# lipovsky-power.net
KiCad netlist of a schematic drawn in EAGLE
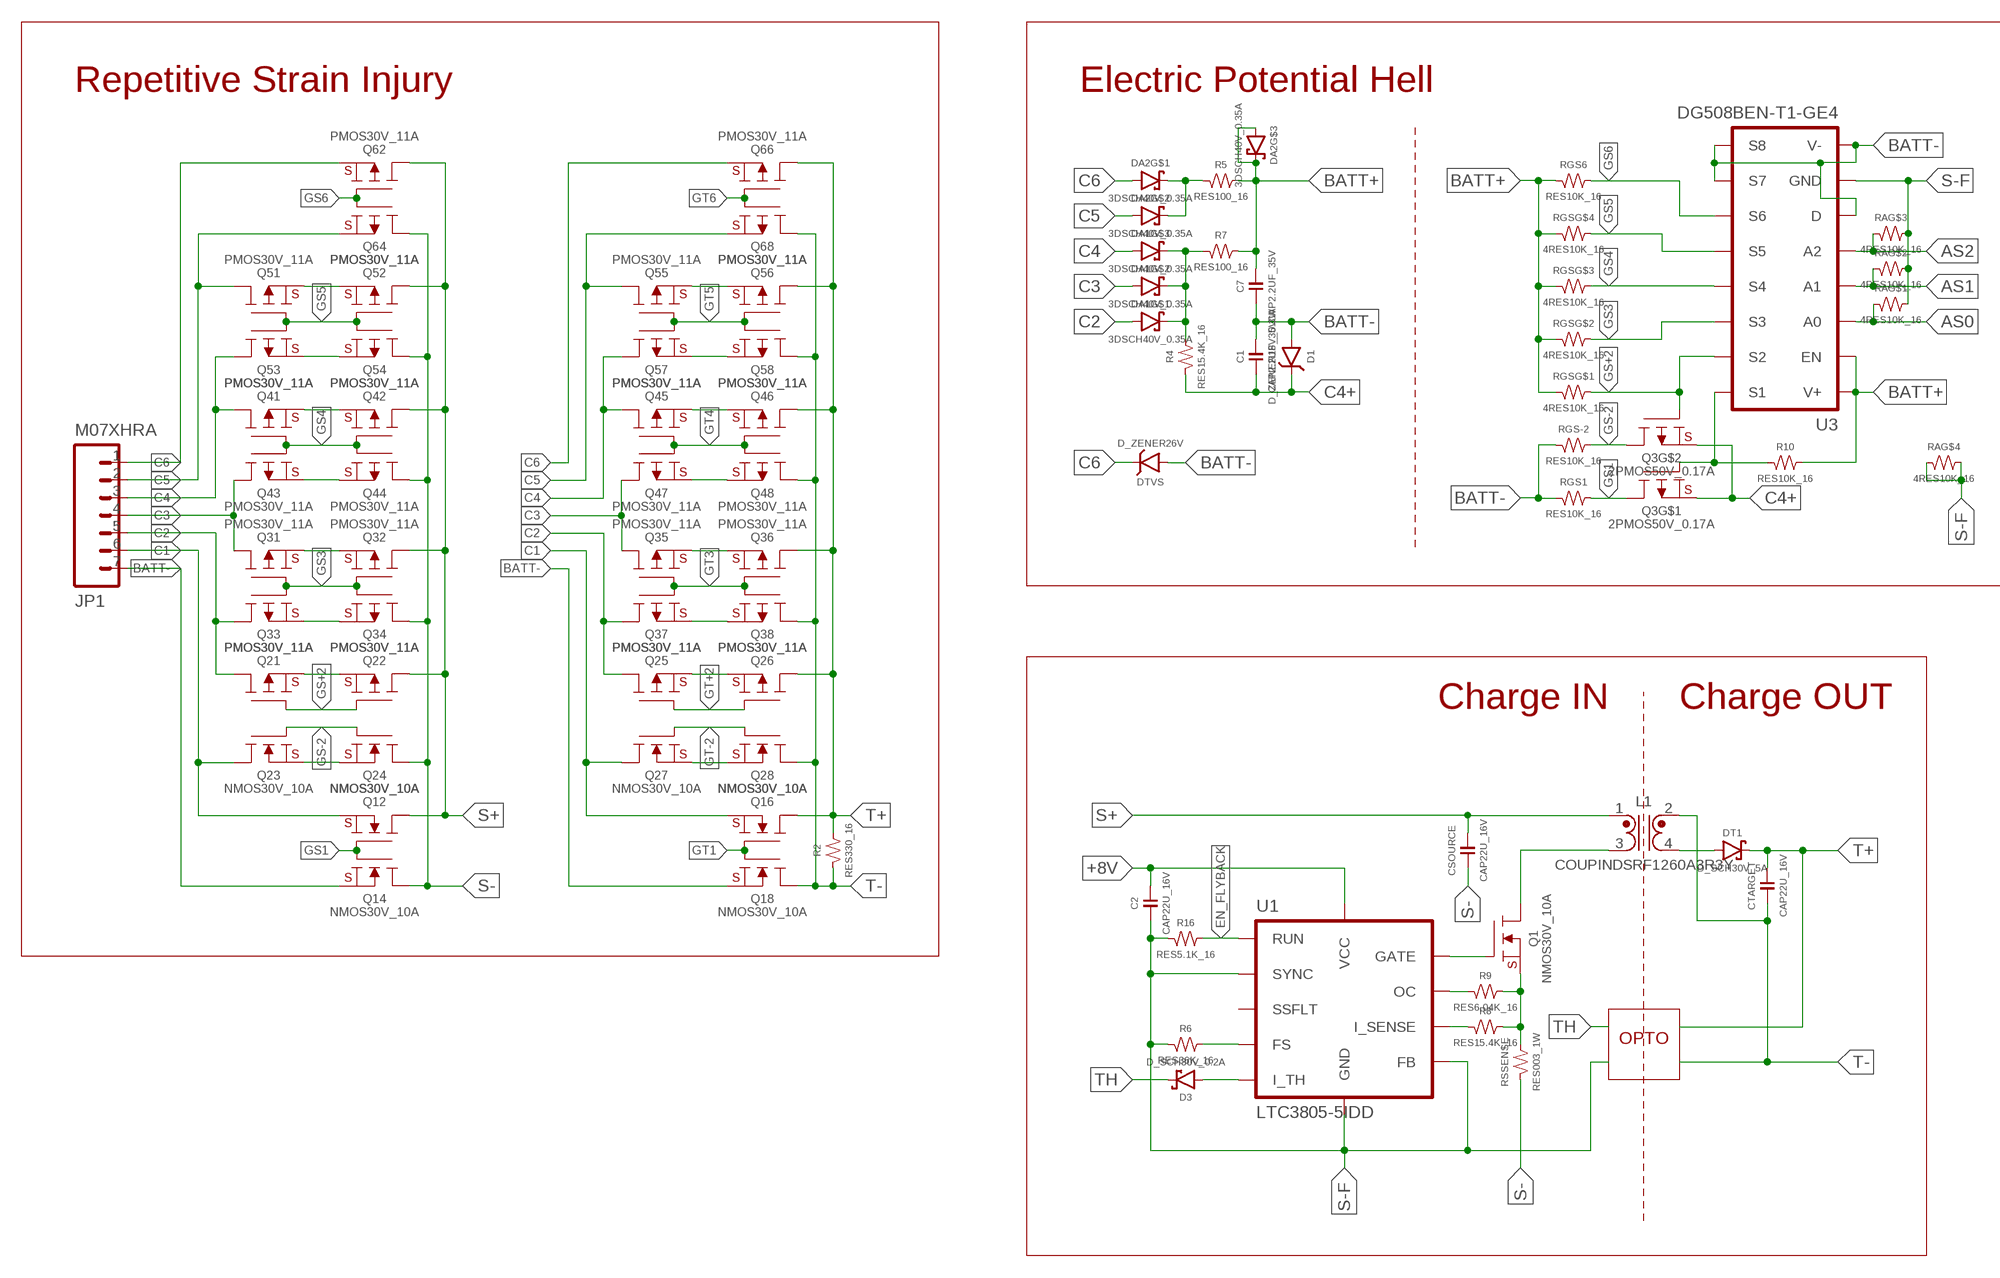
[diagram p0: schematic, sheet 1, part 1 of 2]
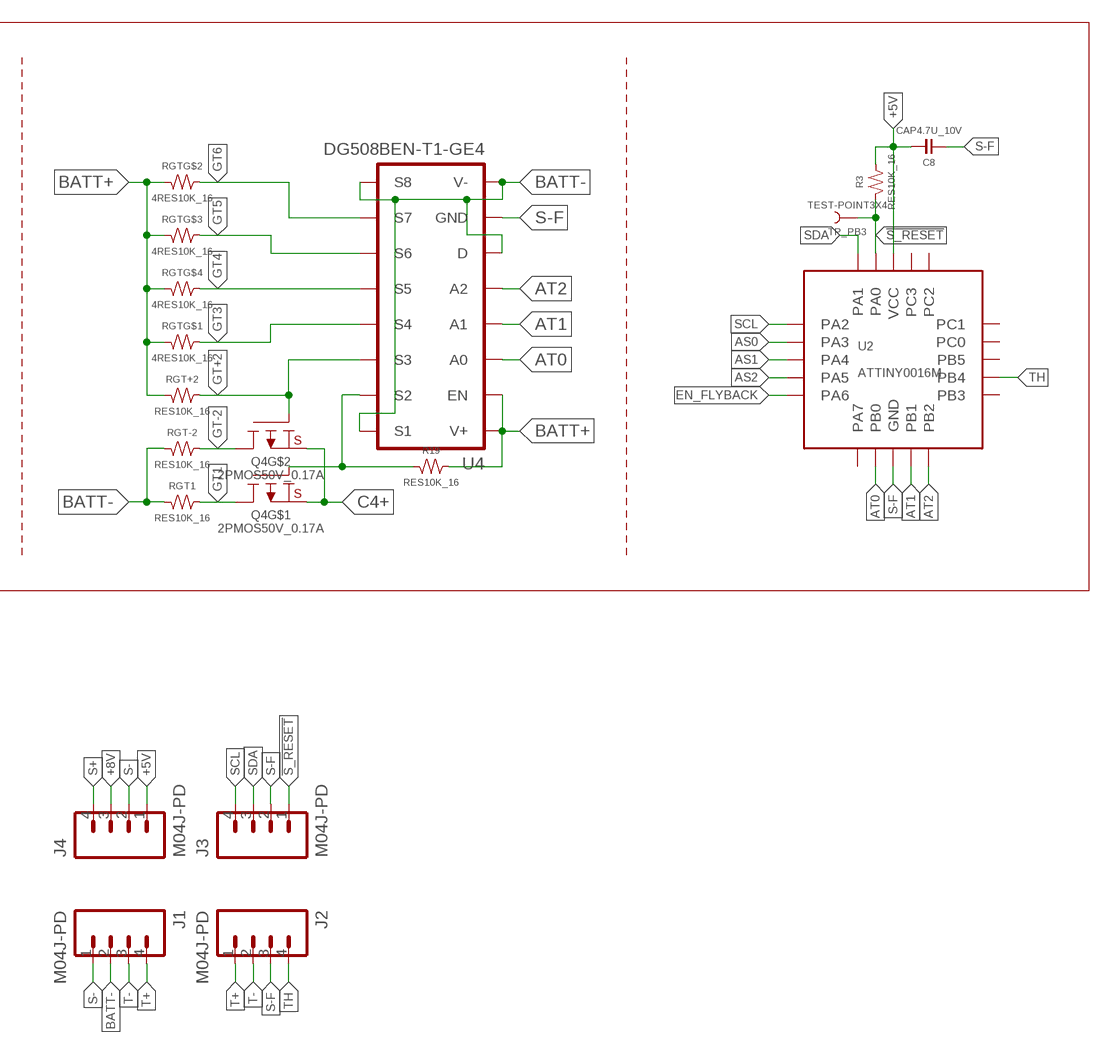
[diagram p1: schematic, sheet 1, part 2 of 2]

(export (version "E")
  (design (tool "Eeschema 10.0.6"))
  (components
    (comp (ref "C1")
      (value "CAP2.2UF_35V")
      (footprint "eagle-import:0402")
      (fields
        (field (name "DIGIKEY_PART_#") "445-9028-1-ND")
        (field (name "MANUFACTURER") "TDK Corporation")
        (field (name "MFG_PART_#") "C1005X5R1V225K050BC")
      )
      (libsource (lib "eagle-import") (part "CAP2.2UF_35V"))
    )
    (comp (ref "C2")
      (value "CAP22U_16V")
      (footprint "eagle-import:0805")
      (fields
        (field (name "DIGIKEY_PART_#") "1276-6780-1-ND")
        (field (name "MANUFACTURER") "Samsung Electro-Mechanics America, Inc.")
        (field (name "MFG_PART_#") "CL21A226MOCLRNC")
      )
      (libsource (lib "eagle-import") (part "CAP22U_16V"))
    )
    (comp (ref "C7")
      (value "CAP2.2UF_35V")
      (footprint "eagle-import:0402")
      (fields
        (field (name "DIGIKEY_PART_#") "445-9028-1-ND")
        (field (name "MANUFACTURER") "TDK Corporation")
        (field (name "MFG_PART_#") "C1005X5R1V225K050BC")
      )
      (libsource (lib "eagle-import") (part "CAP2.2UF_35V"))
    )
    (comp (ref "C8")
      (value "CAP4.7U_10V")
      (footprint "eagle-import:0603")
      (fields
        (field (name "DIGIKEY_PART_#") "587-1441-1-ND")
        (field (name "MANUFACTURER") "Taiyo Yuden")
        (field (name "MFG_PART_#") "LMK107BJ475KA-T")
      )
      (libsource (lib "eagle-import") (part "CAP4.7U_10V"))
    )
    (comp (ref "CSOURCE")
      (value "CAP22U_16V")
      (footprint "eagle-import:0805")
      (fields
        (field (name "DIGIKEY_PART_#") "1276-6780-1-ND")
        (field (name "MANUFACTURER") "Samsung Electro-Mechanics America, Inc.")
        (field (name "MFG_PART_#") "CL21A226MOCLRNC")
      )
      (libsource (lib "eagle-import") (part "CAP22U_16V"))
    )
    (comp (ref "CTARGET")
      (value "CAP22U_16V")
      (footprint "eagle-import:0805")
      (fields
        (field (name "DIGIKEY_PART_#") "1276-6780-1-ND")
        (field (name "MANUFACTURER") "Samsung Electro-Mechanics America, Inc.")
        (field (name "MFG_PART_#") "CL21A226MOCLRNC")
      )
      (libsource (lib "eagle-import") (part "CAP22U_16V"))
    )
    (comp (ref "D1")
      (value "D_ZENER18V_0.3W")
      (footprint "eagle-import:SOD323+")
      (fields
        (field (name "DIGIKEY_PART_#") "MM3Z18VT1GOSCT-ND")
        (field (name "MANUFACTURER") "ON Semiconductor")
        (field (name "MFG_PART_#") "MM3Z18VT1G")
      )
      (libsource (lib "eagle-import") (part "D_ZENER18V_0.3W"))
    )
    (comp (ref "D3")
      (value "D_SCH30V_0.2A")
      (footprint "eagle-import:SOD523+")
      (fields
        (field (name "DIGIKEY_PART_#") "RB531SM-30T2RCT-ND")
        (field (name "MANUFACTURER") "Rohm Semiconductor")
        (field (name "MFG_PART_#") "RB531SM-30T2R")
      )
      (libsource (lib "eagle-import") (part "D_SCH30V_0.2A"))
    )
    (comp (ref "DA1")
      (value "3DSCH40V_0.35A")
      (footprint "eagle-import:SOT-363")
      (fields
        (field (name "DIGIKEY_PART_#") "SD103ATW-FDICT-ND")
        (field (name "MANUFACTURER") "Diodes Incorporated")
        (field (name "MFG_PART_#") "SD103ATW-7-F")
      )
      (libsource (lib "eagle-import") (part "3DSCH40V_0.35A"))
    )
    (comp (ref "DA2")
      (value "3DSCH40V_0.35A")
      (footprint "eagle-import:SOT-363")
      (fields
        (field (name "DIGIKEY_PART_#") "SD103ATW-FDICT-ND")
        (field (name "MANUFACTURER") "Diodes Incorporated")
        (field (name "MFG_PART_#") "SD103ATW-7-F")
      )
      (libsource (lib "eagle-import") (part "3DSCH40V_0.35A"))
    )
    (comp (ref "DT1")
      (value "D_SCH30V_5A")
      (footprint "eagle-import:SOD-128")
      (fields
        (field (name "DIGIKEY_PART_#") "1727-5317-1-ND")
        (field (name "MANUFACTURER") "Nexperia USA Inc.")
        (field (name "MFG_PART_#") "PMEG3050EP,115")
      )
      (libsource (lib "eagle-import") (part "D_SCH30V_5A"))
    )
    (comp (ref "DTVS")
      (value "D_ZENER26V")
      (footprint "eagle-import:2-UDFN")
      (fields
        (field (name "DIGIKEY_PART_#") "D26V0H1U2LP20-7DICT-ND")
        (field (name "MANUFACTURER") "Diodes Incorporated")
        (field (name "MFG_PART_#") "D26V0H1U2LP20-7")
      )
      (libsource (lib "eagle-import") (part "D_ZENER26V"))
    )
    (comp (ref "J1")
      (value "M04J-PD")
      (footprint "eagle-import:1X04_929J")
      (fields
        (field (name "DIGIKEY_PART_#") "801-87-004-10-012101-ND")
        (field (name "MANUFACTURER") "Preci-Dip")
        (field (name "MFG_PART_#") "801-87-004-10-012101")
      )
      (libsource (lib "eagle-import") (part "M04J-PD"))
    )
    (comp (ref "J2")
      (value "M04J-PD")
      (footprint "eagle-import:1X04_929J")
      (fields
        (field (name "DIGIKEY_PART_#") "801-87-004-10-012101-ND")
        (field (name "MANUFACTURER") "Preci-Dip")
        (field (name "MFG_PART_#") "801-87-004-10-012101")
      )
      (libsource (lib "eagle-import") (part "M04J-PD"))
    )
    (comp (ref "J3")
      (value "M04J-PD")
      (footprint "eagle-import:1X04_929J")
      (fields
        (field (name "DIGIKEY_PART_#") "801-87-004-10-012101-ND")
        (field (name "MANUFACTURER") "Preci-Dip")
        (field (name "MFG_PART_#") "801-87-004-10-012101")
      )
      (libsource (lib "eagle-import") (part "M04J-PD"))
    )
    (comp (ref "J4")
      (value "M04J-PD")
      (footprint "eagle-import:1X04_929J")
      (fields
        (field (name "DIGIKEY_PART_#") "801-87-004-10-012101-ND")
        (field (name "MANUFACTURER") "Preci-Dip")
        (field (name "MFG_PART_#") "801-87-004-10-012101")
      )
      (libsource (lib "eagle-import") (part "M04J-PD"))
    )
    (comp (ref "JP1")
      (value "M07XHRA")
      (footprint "eagle-import:XH07-RA")
      (fields
        (field (name "DIGIKEY_PART_#") "455-2240-ND")
        (field (name "MANUFACTURER") "JST Sales America Inc.")
        (field (name "MFG_PART_#") "S7B-XH-A(LF)(SN)")
      )
      (libsource (lib "eagle-import") (part "M07XHRA"))
    )
    (comp (ref "L1")
      (value "COUPINDSRF1260A3R3Y")
      (footprint "eagle-import:SRF1260A")
      (fields
        (field (name "DIGIKEY_PART_#") "SRF1260A-3R3YCT-ND")
        (field (name "MANUFACTURER") "Bourns Inc.")
        (field (name "MFG_PART_#") "SRF1260A-3R3Y")
      )
      (libsource (lib "eagle-import") (part "COUPINDSRF1260A3R3Y"))
    )
    (comp (ref "Q1")
      (value "NMOS30V_10A")
      (footprint "eagle-import:6-POWERWDFN")
      (fields
        (field (name "DIGIKEY_PART_#") "FDMA7670CT-ND")
        (field (name "MANUFACTURER") "Fairchild Semiconductor")
        (field (name "MFG_PART_#") "FDMA7670")
      )
      (libsource (lib "eagle-import") (part "NMOS30V_10A"))
    )
    (comp (ref "Q3")
      (value "2PMOS50V_0.17A")
      (footprint "eagle-import:SOT-666")
      (fields
        (field (name "DIGIKEY_PART_#") "568-10474-1-ND")
        (field (name "MANUFACTURER") "NXP Semiconductors")
        (field (name "MFG_PART_#") "BSS84AKV,115")
      )
      (libsource (lib "eagle-import") (part "2PMOS50V_0.17A"))
    )
    (comp (ref "Q4")
      (value "2PMOS50V_0.17A")
      (footprint "eagle-import:SOT-666")
      (fields
        (field (name "DIGIKEY_PART_#") "568-10474-1-ND")
        (field (name "MANUFACTURER") "NXP Semiconductors")
        (field (name "MFG_PART_#") "BSS84AKV,115")
      )
      (libsource (lib "eagle-import") (part "2PMOS50V_0.17A"))
    )
    (comp (ref "Q12")
      (value "NMOS30V_10A")
      (footprint "eagle-import:6-POWERWDFN")
      (fields
        (field (name "DIGIKEY_PART_#") "FDMA7670CT-ND")
        (field (name "MANUFACTURER") "Fairchild Semiconductor")
        (field (name "MFG_PART_#") "FDMA7670")
      )
      (libsource (lib "eagle-import") (part "NMOS30V_10A"))
    )
    (comp (ref "Q14")
      (value "NMOS30V_10A")
      (footprint "eagle-import:6-POWERWDFN")
      (fields
        (field (name "DIGIKEY_PART_#") "FDMA7670CT-ND")
        (field (name "MANUFACTURER") "Fairchild Semiconductor")
        (field (name "MFG_PART_#") "FDMA7670")
      )
      (libsource (lib "eagle-import") (part "NMOS30V_10A"))
    )
    (comp (ref "Q16")
      (value "NMOS30V_10A")
      (footprint "eagle-import:6-POWERWDFN")
      (fields
        (field (name "DIGIKEY_PART_#") "FDMA7670CT-ND")
        (field (name "MANUFACTURER") "Fairchild Semiconductor")
        (field (name "MFG_PART_#") "FDMA7670")
      )
      (libsource (lib "eagle-import") (part "NMOS30V_10A"))
    )
    (comp (ref "Q18")
      (value "NMOS30V_10A")
      (footprint "eagle-import:6-POWERWDFN")
      (fields
        (field (name "DIGIKEY_PART_#") "FDMA7670CT-ND")
        (field (name "MANUFACTURER") "Fairchild Semiconductor")
        (field (name "MFG_PART_#") "FDMA7670")
      )
      (libsource (lib "eagle-import") (part "NMOS30V_10A"))
    )
    (comp (ref "Q21")
      (value "PMOS30V_11A")
      (footprint "eagle-import:6-POWERWDFN")
      (fields
        (field (name "DIGIKEY_PART_#") "FDMA6676PZCT-ND")
        (field (name "MANUFACTURER") "Fairchild Semiconductor")
        (field (name "MFG_PART_#") "FDMA6676PZ")
      )
      (libsource (lib "eagle-import") (part "PMOS30V_11A"))
    )
    (comp (ref "Q22")
      (value "PMOS30V_11A")
      (footprint "eagle-import:6-POWERWDFN")
      (fields
        (field (name "DIGIKEY_PART_#") "FDMA6676PZCT-ND")
        (field (name "MANUFACTURER") "Fairchild Semiconductor")
        (field (name "MFG_PART_#") "FDMA6676PZ")
      )
      (libsource (lib "eagle-import") (part "PMOS30V_11A"))
    )
    (comp (ref "Q23")
      (value "NMOS30V_10A")
      (footprint "eagle-import:6-POWERWDFN")
      (fields
        (field (name "DIGIKEY_PART_#") "FDMA7670CT-ND")
        (field (name "MANUFACTURER") "Fairchild Semiconductor")
        (field (name "MFG_PART_#") "FDMA7670")
      )
      (libsource (lib "eagle-import") (part "NMOS30V_10A"))
    )
    (comp (ref "Q24")
      (value "NMOS30V_10A")
      (footprint "eagle-import:6-POWERWDFN")
      (fields
        (field (name "DIGIKEY_PART_#") "FDMA7670CT-ND")
        (field (name "MANUFACTURER") "Fairchild Semiconductor")
        (field (name "MFG_PART_#") "FDMA7670")
      )
      (libsource (lib "eagle-import") (part "NMOS30V_10A"))
    )
    (comp (ref "Q25")
      (value "PMOS30V_11A")
      (footprint "eagle-import:6-POWERWDFN")
      (fields
        (field (name "DIGIKEY_PART_#") "FDMA6676PZCT-ND")
        (field (name "MANUFACTURER") "Fairchild Semiconductor")
        (field (name "MFG_PART_#") "FDMA6676PZ")
      )
      (libsource (lib "eagle-import") (part "PMOS30V_11A"))
    )
    (comp (ref "Q26")
      (value "PMOS30V_11A")
      (footprint "eagle-import:6-POWERWDFN")
      (fields
        (field (name "DIGIKEY_PART_#") "FDMA6676PZCT-ND")
        (field (name "MANUFACTURER") "Fairchild Semiconductor")
        (field (name "MFG_PART_#") "FDMA6676PZ")
      )
      (libsource (lib "eagle-import") (part "PMOS30V_11A"))
    )
    (comp (ref "Q27")
      (value "NMOS30V_10A")
      (footprint "eagle-import:6-POWERWDFN")
      (fields
        (field (name "DIGIKEY_PART_#") "FDMA7670CT-ND")
        (field (name "MANUFACTURER") "Fairchild Semiconductor")
        (field (name "MFG_PART_#") "FDMA7670")
      )
      (libsource (lib "eagle-import") (part "NMOS30V_10A"))
    )
    (comp (ref "Q28")
      (value "NMOS30V_10A")
      (footprint "eagle-import:6-POWERWDFN")
      (fields
        (field (name "DIGIKEY_PART_#") "FDMA7670CT-ND")
        (field (name "MANUFACTURER") "Fairchild Semiconductor")
        (field (name "MFG_PART_#") "FDMA7670")
      )
      (libsource (lib "eagle-import") (part "NMOS30V_10A"))
    )
    (comp (ref "Q31")
      (value "PMOS30V_11A")
      (footprint "eagle-import:6-POWERWDFN")
      (fields
        (field (name "DIGIKEY_PART_#") "FDMA6676PZCT-ND")
        (field (name "MANUFACTURER") "Fairchild Semiconductor")
        (field (name "MFG_PART_#") "FDMA6676PZ")
      )
      (libsource (lib "eagle-import") (part "PMOS30V_11A"))
    )
    (comp (ref "Q32")
      (value "PMOS30V_11A")
      (footprint "eagle-import:6-POWERWDFN")
      (fields
        (field (name "DIGIKEY_PART_#") "FDMA6676PZCT-ND")
        (field (name "MANUFACTURER") "Fairchild Semiconductor")
        (field (name "MFG_PART_#") "FDMA6676PZ")
      )
      (libsource (lib "eagle-import") (part "PMOS30V_11A"))
    )
    (comp (ref "Q33")
      (value "PMOS30V_11A")
      (footprint "eagle-import:6-POWERWDFN")
      (fields
        (field (name "DIGIKEY_PART_#") "FDMA6676PZCT-ND")
        (field (name "MANUFACTURER") "Fairchild Semiconductor")
        (field (name "MFG_PART_#") "FDMA6676PZ")
      )
      (libsource (lib "eagle-import") (part "PMOS30V_11A"))
    )
    (comp (ref "Q34")
      (value "PMOS30V_11A")
      (footprint "eagle-import:6-POWERWDFN")
      (fields
        (field (name "DIGIKEY_PART_#") "FDMA6676PZCT-ND")
        (field (name "MANUFACTURER") "Fairchild Semiconductor")
        (field (name "MFG_PART_#") "FDMA6676PZ")
      )
      (libsource (lib "eagle-import") (part "PMOS30V_11A"))
    )
    (comp (ref "Q35")
      (value "PMOS30V_11A")
      (footprint "eagle-import:6-POWERWDFN")
      (fields
        (field (name "DIGIKEY_PART_#") "FDMA6676PZCT-ND")
        (field (name "MANUFACTURER") "Fairchild Semiconductor")
        (field (name "MFG_PART_#") "FDMA6676PZ")
      )
      (libsource (lib "eagle-import") (part "PMOS30V_11A"))
    )
    (comp (ref "Q36")
      (value "PMOS30V_11A")
      (footprint "eagle-import:6-POWERWDFN")
      (fields
        (field (name "DIGIKEY_PART_#") "FDMA6676PZCT-ND")
        (field (name "MANUFACTURER") "Fairchild Semiconductor")
        (field (name "MFG_PART_#") "FDMA6676PZ")
      )
      (libsource (lib "eagle-import") (part "PMOS30V_11A"))
    )
    (comp (ref "Q37")
      (value "PMOS30V_11A")
      (footprint "eagle-import:6-POWERWDFN")
      (fields
        (field (name "DIGIKEY_PART_#") "FDMA6676PZCT-ND")
        (field (name "MANUFACTURER") "Fairchild Semiconductor")
        (field (name "MFG_PART_#") "FDMA6676PZ")
      )
      (libsource (lib "eagle-import") (part "PMOS30V_11A"))
    )
    (comp (ref "Q38")
      (value "PMOS30V_11A")
      (footprint "eagle-import:6-POWERWDFN")
      (fields
        (field (name "DIGIKEY_PART_#") "FDMA6676PZCT-ND")
        (field (name "MANUFACTURER") "Fairchild Semiconductor")
        (field (name "MFG_PART_#") "FDMA6676PZ")
      )
      (libsource (lib "eagle-import") (part "PMOS30V_11A"))
    )
    (comp (ref "Q41")
      (value "PMOS30V_11A")
      (footprint "eagle-import:6-POWERWDFN")
      (fields
        (field (name "DIGIKEY_PART_#") "FDMA6676PZCT-ND")
        (field (name "MANUFACTURER") "Fairchild Semiconductor")
        (field (name "MFG_PART_#") "FDMA6676PZ")
      )
      (libsource (lib "eagle-import") (part "PMOS30V_11A"))
    )
    (comp (ref "Q42")
      (value "PMOS30V_11A")
      (footprint "eagle-import:6-POWERWDFN")
      (fields
        (field (name "DIGIKEY_PART_#") "FDMA6676PZCT-ND")
        (field (name "MANUFACTURER") "Fairchild Semiconductor")
        (field (name "MFG_PART_#") "FDMA6676PZ")
      )
      (libsource (lib "eagle-import") (part "PMOS30V_11A"))
    )
    (comp (ref "Q43")
      (value "PMOS30V_11A")
      (footprint "eagle-import:6-POWERWDFN")
      (fields
        (field (name "DIGIKEY_PART_#") "FDMA6676PZCT-ND")
        (field (name "MANUFACTURER") "Fairchild Semiconductor")
        (field (name "MFG_PART_#") "FDMA6676PZ")
      )
      (libsource (lib "eagle-import") (part "PMOS30V_11A"))
    )
    (comp (ref "Q44")
      (value "PMOS30V_11A")
      (footprint "eagle-import:6-POWERWDFN")
      (fields
        (field (name "DIGIKEY_PART_#") "FDMA6676PZCT-ND")
        (field (name "MANUFACTURER") "Fairchild Semiconductor")
        (field (name "MFG_PART_#") "FDMA6676PZ")
      )
      (libsource (lib "eagle-import") (part "PMOS30V_11A"))
    )
    (comp (ref "Q45")
      (value "PMOS30V_11A")
      (footprint "eagle-import:6-POWERWDFN")
      (fields
        (field (name "DIGIKEY_PART_#") "FDMA6676PZCT-ND")
        (field (name "MANUFACTURER") "Fairchild Semiconductor")
        (field (name "MFG_PART_#") "FDMA6676PZ")
      )
      (libsource (lib "eagle-import") (part "PMOS30V_11A"))
    )
    (comp (ref "Q46")
      (value "PMOS30V_11A")
      (footprint "eagle-import:6-POWERWDFN")
      (fields
        (field (name "DIGIKEY_PART_#") "FDMA6676PZCT-ND")
        (field (name "MANUFACTURER") "Fairchild Semiconductor")
        (field (name "MFG_PART_#") "FDMA6676PZ")
      )
      (libsource (lib "eagle-import") (part "PMOS30V_11A"))
    )
    (comp (ref "Q47")
      (value "PMOS30V_11A")
      (footprint "eagle-import:6-POWERWDFN")
      (fields
        (field (name "DIGIKEY_PART_#") "FDMA6676PZCT-ND")
        (field (name "MANUFACTURER") "Fairchild Semiconductor")
        (field (name "MFG_PART_#") "FDMA6676PZ")
      )
      (libsource (lib "eagle-import") (part "PMOS30V_11A"))
    )
    (comp (ref "Q48")
      (value "PMOS30V_11A")
      (footprint "eagle-import:6-POWERWDFN")
      (fields
        (field (name "DIGIKEY_PART_#") "FDMA6676PZCT-ND")
        (field (name "MANUFACTURER") "Fairchild Semiconductor")
        (field (name "MFG_PART_#") "FDMA6676PZ")
      )
      (libsource (lib "eagle-import") (part "PMOS30V_11A"))
    )
    (comp (ref "Q51")
      (value "PMOS30V_11A")
      (footprint "eagle-import:6-POWERWDFN")
      (fields
        (field (name "DIGIKEY_PART_#") "FDMA6676PZCT-ND")
        (field (name "MANUFACTURER") "Fairchild Semiconductor")
        (field (name "MFG_PART_#") "FDMA6676PZ")
      )
      (libsource (lib "eagle-import") (part "PMOS30V_11A"))
    )
    (comp (ref "Q52")
      (value "PMOS30V_11A")
      (footprint "eagle-import:6-POWERWDFN")
      (fields
        (field (name "DIGIKEY_PART_#") "FDMA6676PZCT-ND")
        (field (name "MANUFACTURER") "Fairchild Semiconductor")
        (field (name "MFG_PART_#") "FDMA6676PZ")
      )
      (libsource (lib "eagle-import") (part "PMOS30V_11A"))
    )
    (comp (ref "Q53")
      (value "PMOS30V_11A")
      (footprint "eagle-import:6-POWERWDFN")
      (fields
        (field (name "DIGIKEY_PART_#") "FDMA6676PZCT-ND")
        (field (name "MANUFACTURER") "Fairchild Semiconductor")
        (field (name "MFG_PART_#") "FDMA6676PZ")
      )
      (libsource (lib "eagle-import") (part "PMOS30V_11A"))
    )
    (comp (ref "Q54")
      (value "PMOS30V_11A")
      (footprint "eagle-import:6-POWERWDFN")
      (fields
        (field (name "DIGIKEY_PART_#") "FDMA6676PZCT-ND")
        (field (name "MANUFACTURER") "Fairchild Semiconductor")
        (field (name "MFG_PART_#") "FDMA6676PZ")
      )
      (libsource (lib "eagle-import") (part "PMOS30V_11A"))
    )
    (comp (ref "Q55")
      (value "PMOS30V_11A")
      (footprint "eagle-import:6-POWERWDFN")
      (fields
        (field (name "DIGIKEY_PART_#") "FDMA6676PZCT-ND")
        (field (name "MANUFACTURER") "Fairchild Semiconductor")
        (field (name "MFG_PART_#") "FDMA6676PZ")
      )
      (libsource (lib "eagle-import") (part "PMOS30V_11A"))
    )
    (comp (ref "Q56")
      (value "PMOS30V_11A")
      (footprint "eagle-import:6-POWERWDFN")
      (fields
        (field (name "DIGIKEY_PART_#") "FDMA6676PZCT-ND")
        (field (name "MANUFACTURER") "Fairchild Semiconductor")
        (field (name "MFG_PART_#") "FDMA6676PZ")
      )
      (libsource (lib "eagle-import") (part "PMOS30V_11A"))
    )
    (comp (ref "Q57")
      (value "PMOS30V_11A")
      (footprint "eagle-import:6-POWERWDFN")
      (fields
        (field (name "DIGIKEY_PART_#") "FDMA6676PZCT-ND")
        (field (name "MANUFACTURER") "Fairchild Semiconductor")
        (field (name "MFG_PART_#") "FDMA6676PZ")
      )
      (libsource (lib "eagle-import") (part "PMOS30V_11A"))
    )
    (comp (ref "Q58")
      (value "PMOS30V_11A")
      (footprint "eagle-import:6-POWERWDFN")
      (fields
        (field (name "DIGIKEY_PART_#") "FDMA6676PZCT-ND")
        (field (name "MANUFACTURER") "Fairchild Semiconductor")
        (field (name "MFG_PART_#") "FDMA6676PZ")
      )
      (libsource (lib "eagle-import") (part "PMOS30V_11A"))
    )
    (comp (ref "Q62")
      (value "PMOS30V_11A")
      (footprint "eagle-import:6-POWERWDFN")
      (fields
        (field (name "DIGIKEY_PART_#") "FDMA6676PZCT-ND")
        (field (name "MANUFACTURER") "Fairchild Semiconductor")
        (field (name "MFG_PART_#") "FDMA6676PZ")
      )
      (libsource (lib "eagle-import") (part "PMOS30V_11A"))
    )
    (comp (ref "Q64")
      (value "PMOS30V_11A")
      (footprint "eagle-import:6-POWERWDFN")
      (fields
        (field (name "DIGIKEY_PART_#") "FDMA6676PZCT-ND")
        (field (name "MANUFACTURER") "Fairchild Semiconductor")
        (field (name "MFG_PART_#") "FDMA6676PZ")
      )
      (libsource (lib "eagle-import") (part "PMOS30V_11A"))
    )
    (comp (ref "Q66")
      (value "PMOS30V_11A")
      (footprint "eagle-import:6-POWERWDFN")
      (fields
        (field (name "DIGIKEY_PART_#") "FDMA6676PZCT-ND")
        (field (name "MANUFACTURER") "Fairchild Semiconductor")
        (field (name "MFG_PART_#") "FDMA6676PZ")
      )
      (libsource (lib "eagle-import") (part "PMOS30V_11A"))
    )
    (comp (ref "Q68")
      (value "PMOS30V_11A")
      (footprint "eagle-import:6-POWERWDFN")
      (fields
        (field (name "DIGIKEY_PART_#") "FDMA6676PZCT-ND")
        (field (name "MANUFACTURER") "Fairchild Semiconductor")
        (field (name "MFG_PART_#") "FDMA6676PZ")
      )
      (libsource (lib "eagle-import") (part "PMOS30V_11A"))
    )
    (comp (ref "R2")
      (value "RES330_16")
      (footprint "eagle-import:0402")
      (fields
        (field (name "DIGIKEY_PART_#") "541-330LCT-ND")
        (field (name "MANUFACTURER") "Vishay Dale")
        (field (name "MFG_PART_#") "CRCW0402330RFKED")
      )
      (libsource (lib "eagle-import") (part "RES330_16"))
    )
    (comp (ref "R3")
      (value "RES10K_16")
      (footprint "eagle-import:0402")
      (fields
        (field (name "DIGIKEY_PART_#") "541-10.0KLCT-ND")
        (field (name "MANUFACTURER") "Vishay Dale")
        (field (name "MFG_PART_#") "CRCW040210K0FKED")
      )
      (libsource (lib "eagle-import") (part "RES10K_16"))
    )
    (comp (ref "R4")
      (value "RES15.4K_16")
      (footprint "eagle-import:0402")
      (fields
        (field (name "DIGIKEY_PART_#") "541-15.4KLCT-ND")
        (field (name "MANUFACTURER") "Vishay Dale")
        (field (name "MFG_PART_#") "CRCW040215K4FKED")
      )
      (libsource (lib "eagle-import") (part "RES15.4K_16"))
    )
    (comp (ref "R5")
      (value "RES100_16")
      (footprint "eagle-import:0402")
      (fields
        (field (name "DIGIKEY_PART_#") "541-100LCT-ND")
        (field (name "MANUFACTURER") "Vishay Dale")
        (field (name "MFG_PART_#") "CRCW0402100RFKED")
      )
      (libsource (lib "eagle-import") (part "RES100_16"))
    )
    (comp (ref "R6")
      (value "RES36K_16")
      (footprint "eagle-import:0402")
      (fields
        (field (name "DIGIKEY_PART_#") "541-36.0KLCT-ND")
        (field (name "MANUFACTURER") "Vishay Dale")
        (field (name "MFG_PART_#") "CRCW040236K0FKED")
      )
      (libsource (lib "eagle-import") (part "RES36K_16"))
    )
    (comp (ref "R7")
      (value "RES100_16")
      (footprint "eagle-import:0402")
      (fields
        (field (name "DIGIKEY_PART_#") "541-100LCT-ND")
        (field (name "MANUFACTURER") "Vishay Dale")
        (field (name "MFG_PART_#") "CRCW0402100RFKED")
      )
      (libsource (lib "eagle-import") (part "RES100_16"))
    )
    (comp (ref "R8")
      (value "RES15.4K_16")
      (footprint "eagle-import:0402")
      (fields
        (field (name "DIGIKEY_PART_#") "541-15.4KLCT-ND")
        (field (name "MANUFACTURER") "Vishay Dale")
        (field (name "MFG_PART_#") "CRCW040215K4FKED")
      )
      (libsource (lib "eagle-import") (part "RES15.4K_16"))
    )
    (comp (ref "R9")
      (value "RES6.04K_16")
      (footprint "eagle-import:0402")
      (fields
        (field (name "DIGIKEY_PART_#") "541-6.04KLCT-ND")
        (field (name "MANUFACTURER") "Vishay Dale")
        (field (name "MFG_PART_#") "CRCW04026K04FKED")
      )
      (libsource (lib "eagle-import") (part "RES6.04K_16"))
    )
    (comp (ref "R10")
      (value "RES10K_16")
      (footprint "eagle-import:0402")
      (fields
        (field (name "DIGIKEY_PART_#") "541-10.0KLCT-ND")
        (field (name "MANUFACTURER") "Vishay Dale")
        (field (name "MFG_PART_#") "CRCW040210K0FKED")
      )
      (libsource (lib "eagle-import") (part "RES10K_16"))
    )
    (comp (ref "R16")
      (value "RES5.1K_16")
      (footprint "eagle-import:0402")
      (fields
        (field (name "DIGIKEY_PART_#") "541-5.10KLCT-ND")
        (field (name "MANUFACTURER") "Vishay Dale")
        (field (name "MFG_PART_#") "CRCW04025K10FKED")
      )
      (libsource (lib "eagle-import") (part "RES5.1K_16"))
    )
    (comp (ref "R19")
      (value "RES10K_16")
      (footprint "eagle-import:0402")
      (fields
        (field (name "DIGIKEY_PART_#") "541-10.0KLCT-ND")
        (field (name "MANUFACTURER") "Vishay Dale")
        (field (name "MFG_PART_#") "CRCW040210K0FKED")
      )
      (libsource (lib "eagle-import") (part "RES10K_16"))
    )
    (comp (ref "RA")
      (value "4RES10K_16")
      (footprint "eagle-import:1206-QUAD-LS")
      (fields
        (field (name "DIGIKEY_PART_#") "Y9103CT-ND")
        (field (name "MANUFACTURER") "Panasonic Electronic Components")
        (field (name "MFG_PART_#") "EXB-38V103JV")
      )
      (libsource (lib "eagle-import") (part "4RES10K_16"))
    )
    (comp (ref "RGS")
      (value "4RES10K_16")
      (footprint "eagle-import:1206-QUAD-LS")
      (fields
        (field (name "DIGIKEY_PART_#") "Y9103CT-ND")
        (field (name "MANUFACTURER") "Panasonic Electronic Components")
        (field (name "MFG_PART_#") "EXB-38V103JV")
      )
      (libsource (lib "eagle-import") (part "4RES10K_16"))
    )
    (comp (ref "RGS-2")
      (value "RES10K_16")
      (footprint "eagle-import:0402")
      (fields
        (field (name "DIGIKEY_PART_#") "541-10.0KLCT-ND")
        (field (name "MANUFACTURER") "Vishay Dale")
        (field (name "MFG_PART_#") "CRCW040210K0FKED")
      )
      (libsource (lib "eagle-import") (part "RES10K_16"))
    )
    (comp (ref "RGS1")
      (value "RES10K_16")
      (footprint "eagle-import:0402")
      (fields
        (field (name "DIGIKEY_PART_#") "541-10.0KLCT-ND")
        (field (name "MANUFACTURER") "Vishay Dale")
        (field (name "MFG_PART_#") "CRCW040210K0FKED")
      )
      (libsource (lib "eagle-import") (part "RES10K_16"))
    )
    (comp (ref "RGS6")
      (value "RES10K_16")
      (footprint "eagle-import:0402")
      (fields
        (field (name "DIGIKEY_PART_#") "541-10.0KLCT-ND")
        (field (name "MANUFACTURER") "Vishay Dale")
        (field (name "MFG_PART_#") "CRCW040210K0FKED")
      )
      (libsource (lib "eagle-import") (part "RES10K_16"))
    )
    (comp (ref "RGT")
      (value "4RES10K_16")
      (footprint "eagle-import:1206-QUAD-LS")
      (fields
        (field (name "DIGIKEY_PART_#") "Y9103CT-ND")
        (field (name "MANUFACTURER") "Panasonic Electronic Components")
        (field (name "MFG_PART_#") "EXB-38V103JV")
      )
      (libsource (lib "eagle-import") (part "4RES10K_16"))
    )
    (comp (ref "RGT+2")
      (value "RES10K_16")
      (footprint "eagle-import:0402")
      (fields
        (field (name "DIGIKEY_PART_#") "541-10.0KLCT-ND")
        (field (name "MANUFACTURER") "Vishay Dale")
        (field (name "MFG_PART_#") "CRCW040210K0FKED")
      )
      (libsource (lib "eagle-import") (part "RES10K_16"))
    )
    (comp (ref "RGT-2")
      (value "RES10K_16")
      (footprint "eagle-import:0402")
      (fields
        (field (name "DIGIKEY_PART_#") "541-10.0KLCT-ND")
        (field (name "MANUFACTURER") "Vishay Dale")
        (field (name "MFG_PART_#") "CRCW040210K0FKED")
      )
      (libsource (lib "eagle-import") (part "RES10K_16"))
    )
    (comp (ref "RGT1")
      (value "RES10K_16")
      (footprint "eagle-import:0402")
      (fields
        (field (name "DIGIKEY_PART_#") "541-10.0KLCT-ND")
        (field (name "MANUFACTURER") "Vishay Dale")
        (field (name "MFG_PART_#") "CRCW040210K0FKED")
      )
      (libsource (lib "eagle-import") (part "RES10K_16"))
    )
    (comp (ref "RSSENSE")
      (value "RES003_1W")
      (footprint "eagle-import:1206")
      (fields
        (field (name "DIGIKEY_PART_#") "CSNL1206FT3L00CT-ND")
        (field (name "MANUFACTURER") "Stackpole Electronics Inc.")
        (field (name "MFG_PART_#") "CSNL1206FT3L00")
      )
      (libsource (lib "eagle-import") (part "RES003_1W"))
    )
    (comp (ref "TP_PB3")
      (value "TEST-POINT3X4")
      (footprint "eagle-import:PAD.03X.04")
      (libsource (lib "eagle-import") (part "TEST-POINT3X4"))
    )
    (comp (ref "U1")
      (value "LTC3805-5IDD")
      (footprint "eagle-import:10-WFDFN")
      (fields
        (field (name "DIGIKEY_PART_#") "LTC3805IDD-5#PBF-ND")
        (field (name "MANUFACTURER") "Linear Technology")
        (field (name "MFG_PART_#") "LTC3805IDD-5#PBF")
      )
      (libsource (lib "eagle-import") (part "LTC3805-5IDD"))
    )
    (comp (ref "U2")
      (value "ATTINY0016M")
      (footprint "eagle-import:20-VQFN-2")
      (fields
        (field (name "DIGIKEY_PART_#") "ATTINY1616-MFRCT-ND")
        (field (name "MANUFACTURER") "Microchip Technology")
        (field (name "MFG_PART_#") "ATTINY1616-MFR")
      )
      (libsource (lib "eagle-import") (part "ATTINY0016M"))
    )
    (comp (ref "U3")
      (value "DG508BEN-T1-GE4")
      (footprint "eagle-import:MINIQFN-16L")
      (fields
        (field (name "MANUFACTURER") "Vishay Siliconix")
        (field (name "MOUSER_PART_#") "78-DG508BEN-T1-GE4")
      )
      (libsource (lib "eagle-import") (part "DG508BEN-T1-GE4"))
    )
    (comp (ref "U4")
      (value "DG508BEN-T1-GE4")
      (footprint "eagle-import:MINIQFN-16L")
      (fields
        (field (name "MANUFACTURER") "Vishay Siliconix")
        (field (name "MOUSER_PART_#") "78-DG508BEN-T1-GE4")
      )
      (libsource (lib "eagle-import") (part "DG508BEN-T1-GE4"))
    )
  )
  (nets
    (net (code "1") (name "+5V") (class "Default")
      (node (ref "C8") (pin "2") (pinfunction "2_2") (pintype "passive"))
      (node (ref "J4") (pin "1") (pinfunction "1_1") (pintype "passive"))
      (node (ref "R3") (pin "2") (pinfunction "2_2") (pintype "passive"))
      (node (ref "U2") (pin "4") (pinfunction "VCC_4") (pintype "passive"))
    )
    (net (code "2") (name "+8V") (class "Default")
      (node (ref "C2") (pin "2") (pinfunction "2_2") (pintype "passive"))
      (node (ref "J4") (pin "3") (pinfunction "3_3") (pintype "passive"))
      (node (ref "U1") (pin "7") (pinfunction "VCC_7") (pintype "power_in"))
    )
    (net (code "3") (name "/~{S_RESET}") (class "Default")
      (node (ref "J3") (pin "1") (pinfunction "1_1") (pintype "passive"))
      (node (ref "R3") (pin "1") (pinfunction "1_1") (pintype "passive"))
      (node (ref "TP_PB3") (pin "P$1") (pinfunction "1_P$1") (pintype "bidirectional"))
      (node (ref "U2") (pin "19") (pinfunction "PA0_19") (pintype "passive"))
    )
    (net (code "4") (name "AS0") (class "Default")
      (node (ref "RA") (pin "1") (pinfunction "1_1") (pintype "passive"))
      (node (ref "U2") (pin "2") (pinfunction "PA3_2") (pintype "passive"))
      (node (ref "U3") (pin "15") (pinfunction "A0_15") (pintype "passive"))
    )
    (net (code "5") (name "AS1") (class "Default")
      (node (ref "RA") (pin "2") (pinfunction "1_2") (pintype "passive"))
      (node (ref "U2") (pin "5") (pinfunction "PA4_5") (pintype "passive"))
      (node (ref "U3") (pin "14") (pinfunction "A1_14") (pintype "passive"))
    )
    (net (code "6") (name "AS2") (class "Default")
      (node (ref "RA") (pin "3") (pinfunction "1_3") (pintype "passive"))
      (node (ref "U2") (pin "6") (pinfunction "PA5_6") (pintype "passive"))
      (node (ref "U3") (pin "13") (pinfunction "A2_13") (pintype "passive"))
    )
    (net (code "7") (name "AT0") (class "Default")
      (node (ref "U2") (pin "14") (pinfunction "PB0_14") (pintype "passive"))
      (node (ref "U4") (pin "15") (pinfunction "A0_15") (pintype "passive"))
    )
    (net (code "8") (name "AT1") (class "Default")
      (node (ref "U2") (pin "13") (pinfunction "PB1_13") (pintype "passive"))
      (node (ref "U4") (pin "14") (pinfunction "A1_14") (pintype "passive"))
    )
    (net (code "9") (name "AT2") (class "Default")
      (node (ref "U2") (pin "12") (pinfunction "PB2_12") (pintype "passive"))
      (node (ref "U4") (pin "13") (pinfunction "A2_13") (pintype "passive"))
    )
    (net (code "10") (name "BATT+") (class "Default")
      (node (ref "C7") (pin "2") (pinfunction "2_2") (pintype "passive"))
      (node (ref "DA2") (pin "3") (pinfunction "C_3") (pintype "passive"))
      (node (ref "DA2") (pin "4") (pinfunction "A_4") (pintype "passive"))
      (node (ref "R10") (pin "2") (pinfunction "2_2") (pintype "passive"))
      (node (ref "R19") (pin "2") (pinfunction "2_2") (pintype "passive"))
      (node (ref "R5") (pin "2") (pinfunction "2_2") (pintype "passive"))
      (node (ref "R7") (pin "2") (pinfunction "2_2") (pintype "passive"))
      (node (ref "RGS") (pin "1") (pinfunction "1_1") (pintype "passive"))
      (node (ref "RGS") (pin "2") (pinfunction "1_2") (pintype "passive"))
      (node (ref "RGS") (pin "3") (pinfunction "1_3") (pintype "passive"))
      (node (ref "RGS") (pin "4") (pinfunction "1_4") (pintype "passive"))
      (node (ref "RGS6") (pin "1") (pinfunction "1_1") (pintype "passive"))
      (node (ref "RGT") (pin "1") (pinfunction "1_1") (pintype "passive"))
      (node (ref "RGT") (pin "2") (pinfunction "1_2") (pintype "passive"))
      (node (ref "RGT") (pin "3") (pinfunction "1_3") (pintype "passive"))
      (node (ref "RGT") (pin "4") (pinfunction "1_4") (pintype "passive"))
      (node (ref "RGT+2") (pin "1") (pinfunction "1_1") (pintype "passive"))
      (node (ref "U3") (pin "11") (pinfunction "V+_11") (pintype "passive"))
      (node (ref "U3") (pin "16") (pinfunction "EN_16") (pintype "passive"))
      (node (ref "U4") (pin "11") (pinfunction "V+_11") (pintype "passive"))
      (node (ref "U4") (pin "16") (pinfunction "EN_16") (pintype "passive"))
    )
    (net (code "11") (name "BATT-") (class "Default")
      (node (ref "C1") (pin "2") (pinfunction "2_2") (pintype "passive"))
      (node (ref "C7") (pin "1") (pinfunction "1_1") (pintype "passive"))
      (node (ref "D1") (pin "A") (pinfunction "A_A") (pintype "passive"))
      (node (ref "DTVS") (pin "A") (pinfunction "A_A") (pintype "passive"))
      (node (ref "J1") (pin "2") (pinfunction "2_2") (pintype "passive"))
      (node (ref "JP1") (pin "7") (pinfunction "7_7") (pintype "passive"))
      (node (ref "Q14") (pin "S") (pinfunction "S_S") (pintype "passive"))
      (node (ref "Q18") (pin "S") (pinfunction "S_S") (pintype "passive"))
      (node (ref "RGS-2") (pin "1") (pinfunction "1_1") (pintype "passive"))
      (node (ref "RGS1") (pin "1") (pinfunction "1_1") (pintype "passive"))
      (node (ref "RGT-2") (pin "1") (pinfunction "1_1") (pintype "passive"))
      (node (ref "RGT1") (pin "1") (pinfunction "1_1") (pintype "passive"))
      (node (ref "U3") (pin "1") (pinfunction "V-_1") (pintype "passive"))
      (node (ref "U3") (pin "6") (pinfunction "D_6") (pintype "passive"))
      (node (ref "U3") (pin "7") (pinfunction "S8_7") (pintype "passive"))
      (node (ref "U3") (pin "8") (pinfunction "S7_8") (pintype "passive"))
      (node (ref "U4") (pin "1") (pinfunction "V-_1") (pintype "passive"))
      (node (ref "U4") (pin "2") (pinfunction "S1_2") (pintype "passive"))
      (node (ref "U4") (pin "6") (pinfunction "D_6") (pintype "passive"))
      (node (ref "U4") (pin "7") (pinfunction "S8_7") (pintype "passive"))
    )
    (net (code "12") (name "C1") (class "Default")
      (node (ref "JP1") (pin "6") (pinfunction "6_6") (pintype "passive"))
      (node (ref "Q12") (pin "S") (pinfunction "S_S") (pintype "passive"))
      (node (ref "Q16") (pin "S") (pinfunction "S_S") (pintype "passive"))
      (node (ref "Q23") (pin "D") (pinfunction "D_D") (pintype "passive"))
      (node (ref "Q27") (pin "D") (pinfunction "D_D") (pintype "passive"))
    )
    (net (code "13") (name "C2") (class "Default")
      (node (ref "DA1") (pin "6") (pinfunction "A_6") (pintype "passive"))
      (node (ref "JP1") (pin "5") (pinfunction "5_5") (pintype "passive"))
      (node (ref "Q21") (pin "D") (pinfunction "D_D") (pintype "passive"))
      (node (ref "Q25") (pin "D") (pinfunction "D_D") (pintype "passive"))
      (node (ref "Q33") (pin "D") (pinfunction "D_D") (pintype "passive"))
      (node (ref "Q37") (pin "D") (pinfunction "D_D") (pintype "passive"))
    )
    (net (code "14") (name "C3") (class "Default")
      (node (ref "DA1") (pin "5") (pinfunction "A_5") (pintype "passive"))
      (node (ref "JP1") (pin "4") (pinfunction "4_4") (pintype "passive"))
      (node (ref "Q31") (pin "D") (pinfunction "D_D") (pintype "passive"))
      (node (ref "Q35") (pin "D") (pinfunction "D_D") (pintype "passive"))
      (node (ref "Q43") (pin "D") (pinfunction "D_D") (pintype "passive"))
      (node (ref "Q47") (pin "D") (pinfunction "D_D") (pintype "passive"))
    )
    (net (code "15") (name "C4") (class "Default")
      (node (ref "DA1") (pin "4") (pinfunction "A_4") (pintype "passive"))
      (node (ref "JP1") (pin "3") (pinfunction "3_3") (pintype "passive"))
      (node (ref "Q41") (pin "D") (pinfunction "D_D") (pintype "passive"))
      (node (ref "Q45") (pin "D") (pinfunction "D_D") (pintype "passive"))
      (node (ref "Q53") (pin "D") (pinfunction "D_D") (pintype "passive"))
      (node (ref "Q57") (pin "D") (pinfunction "D_D") (pintype "passive"))
    )
    (net (code "16") (name "C4+") (class "Default")
      (node (ref "C1") (pin "1") (pinfunction "1_1") (pintype "passive"))
      (node (ref "D1") (pin "C") (pinfunction "C_C") (pintype "passive"))
      (node (ref "Q3") (pin "1") (pinfunction "S_1") (pintype "passive"))
      (node (ref "Q3") (pin "4") (pinfunction "S_4") (pintype "passive"))
      (node (ref "Q4") (pin "1") (pinfunction "S_1") (pintype "passive"))
      (node (ref "Q4") (pin "4") (pinfunction "S_4") (pintype "passive"))
      (node (ref "R4") (pin "1") (pinfunction "1_1") (pintype "passive"))
    )
    (net (code "17") (name "C5") (class "Default")
      (node (ref "DA2") (pin "5") (pinfunction "A_5") (pintype "passive"))
      (node (ref "JP1") (pin "2") (pinfunction "2_2") (pintype "passive"))
      (node (ref "Q51") (pin "D") (pinfunction "D_D") (pintype "passive"))
      (node (ref "Q55") (pin "D") (pinfunction "D_D") (pintype "passive"))
      (node (ref "Q64") (pin "S") (pinfunction "S_S") (pintype "passive"))
      (node (ref "Q68") (pin "S") (pinfunction "S_S") (pintype "passive"))
    )
    (net (code "18") (name "C6") (class "Default")
      (node (ref "DA2") (pin "6") (pinfunction "A_6") (pintype "passive"))
      (node (ref "DTVS") (pin "C") (pinfunction "C_C") (pintype "passive"))
      (node (ref "JP1") (pin "1") (pinfunction "1_1") (pintype "passive"))
      (node (ref "Q62") (pin "S") (pinfunction "S_S") (pintype "passive"))
      (node (ref "Q66") (pin "S") (pinfunction "S_S") (pintype "passive"))
    )
    (net (code "19") (name "EN_FLYBACK") (class "Default")
      (node (ref "R16") (pin "2") (pinfunction "2_2") (pintype "passive"))
      (node (ref "U1") (pin "4") (pinfunction "RUN_4") (pintype "passive"))
      (node (ref "U2") (pin "7") (pinfunction "PA6_7") (pintype "passive"))
    )
    (net (code "20") (name "GS+2") (class "Default")
      (node (ref "Q21") (pin "G") (pinfunction "G_G") (pintype "passive"))
      (node (ref "Q22") (pin "G") (pinfunction "G_G") (pintype "passive"))
      (node (ref "Q3") (pin "5") (pinfunction "G_5") (pintype "passive"))
      (node (ref "RGS") (pin "8") (pinfunction "2_8") (pintype "passive"))
      (node (ref "U3") (pin "3") (pinfunction "S2_3") (pintype "passive"))
    )
    (net (code "21") (name "GS-2") (class "Default")
      (node (ref "Q23") (pin "G") (pinfunction "G_G") (pintype "passive"))
      (node (ref "Q24") (pin "G") (pinfunction "G_G") (pintype "passive"))
      (node (ref "Q3") (pin "3") (pinfunction "D_3") (pintype "passive"))
      (node (ref "RGS-2") (pin "2") (pinfunction "2_2") (pintype "passive"))
    )
    (net (code "22") (name "GS1") (class "Default")
      (node (ref "Q12") (pin "G") (pinfunction "G_G") (pintype "passive"))
      (node (ref "Q14") (pin "G") (pinfunction "G_G") (pintype "passive"))
      (node (ref "Q3") (pin "6") (pinfunction "D_6") (pintype "passive"))
      (node (ref "RGS1") (pin "2") (pinfunction "2_2") (pintype "passive"))
    )
    (net (code "23") (name "GS3") (class "Default")
      (node (ref "Q31") (pin "G") (pinfunction "G_G") (pintype "passive"))
      (node (ref "Q32") (pin "G") (pinfunction "G_G") (pintype "passive"))
      (node (ref "Q33") (pin "G") (pinfunction "G_G") (pintype "passive"))
      (node (ref "Q34") (pin "G") (pinfunction "G_G") (pintype "passive"))
      (node (ref "RGS") (pin "7") (pinfunction "2_7") (pintype "passive"))
      (node (ref "U3") (pin "4") (pinfunction "S3_4") (pintype "passive"))
    )
    (net (code "24") (name "GS4") (class "Default")
      (node (ref "Q41") (pin "G") (pinfunction "G_G") (pintype "passive"))
      (node (ref "Q42") (pin "G") (pinfunction "G_G") (pintype "passive"))
      (node (ref "Q43") (pin "G") (pinfunction "G_G") (pintype "passive"))
      (node (ref "Q44") (pin "G") (pinfunction "G_G") (pintype "passive"))
      (node (ref "RGS") (pin "6") (pinfunction "2_6") (pintype "passive"))
      (node (ref "U3") (pin "5") (pinfunction "S4_5") (pintype "passive"))
    )
    (net (code "25") (name "GS5") (class "Default")
      (node (ref "Q51") (pin "G") (pinfunction "G_G") (pintype "passive"))
      (node (ref "Q52") (pin "G") (pinfunction "G_G") (pintype "passive"))
      (node (ref "Q53") (pin "G") (pinfunction "G_G") (pintype "passive"))
      (node (ref "Q54") (pin "G") (pinfunction "G_G") (pintype "passive"))
      (node (ref "RGS") (pin "5") (pinfunction "2_5") (pintype "passive"))
      (node (ref "U3") (pin "10") (pinfunction "S5_10") (pintype "passive"))
    )
    (net (code "26") (name "GS6") (class "Default")
      (node (ref "Q62") (pin "G") (pinfunction "G_G") (pintype "passive"))
      (node (ref "Q64") (pin "G") (pinfunction "G_G") (pintype "passive"))
      (node (ref "RGS6") (pin "2") (pinfunction "2_2") (pintype "passive"))
      (node (ref "U3") (pin "9") (pinfunction "S6_9") (pintype "passive"))
    )
    (net (code "27") (name "GT+2") (class "Default")
      (node (ref "Q25") (pin "G") (pinfunction "G_G") (pintype "passive"))
      (node (ref "Q26") (pin "G") (pinfunction "G_G") (pintype "passive"))
      (node (ref "Q4") (pin "5") (pinfunction "G_5") (pintype "passive"))
      (node (ref "RGT+2") (pin "2") (pinfunction "2_2") (pintype "passive"))
      (node (ref "U4") (pin "4") (pinfunction "S3_4") (pintype "passive"))
    )
    (net (code "28") (name "GT-2") (class "Default")
      (node (ref "Q27") (pin "G") (pinfunction "G_G") (pintype "passive"))
      (node (ref "Q28") (pin "G") (pinfunction "G_G") (pintype "passive"))
      (node (ref "Q4") (pin "3") (pinfunction "D_3") (pintype "passive"))
      (node (ref "RGT-2") (pin "2") (pinfunction "2_2") (pintype "passive"))
    )
    (net (code "29") (name "GT1") (class "Default")
      (node (ref "Q16") (pin "G") (pinfunction "G_G") (pintype "passive"))
      (node (ref "Q18") (pin "G") (pinfunction "G_G") (pintype "passive"))
      (node (ref "Q4") (pin "6") (pinfunction "D_6") (pintype "passive"))
      (node (ref "RGT1") (pin "2") (pinfunction "2_2") (pintype "passive"))
    )
    (net (code "30") (name "GT3") (class "Default")
      (node (ref "Q35") (pin "G") (pinfunction "G_G") (pintype "passive"))
      (node (ref "Q36") (pin "G") (pinfunction "G_G") (pintype "passive"))
      (node (ref "Q37") (pin "G") (pinfunction "G_G") (pintype "passive"))
      (node (ref "Q38") (pin "G") (pinfunction "G_G") (pintype "passive"))
      (node (ref "RGT") (pin "8") (pinfunction "2_8") (pintype "passive"))
      (node (ref "U4") (pin "5") (pinfunction "S4_5") (pintype "passive"))
    )
    (net (code "31") (name "GT4") (class "Default")
      (node (ref "Q45") (pin "G") (pinfunction "G_G") (pintype "passive"))
      (node (ref "Q46") (pin "G") (pinfunction "G_G") (pintype "passive"))
      (node (ref "Q47") (pin "G") (pinfunction "G_G") (pintype "passive"))
      (node (ref "Q48") (pin "G") (pinfunction "G_G") (pintype "passive"))
      (node (ref "RGT") (pin "5") (pinfunction "2_5") (pintype "passive"))
      (node (ref "U4") (pin "10") (pinfunction "S5_10") (pintype "passive"))
    )
    (net (code "32") (name "GT5") (class "Default")
      (node (ref "Q55") (pin "G") (pinfunction "G_G") (pintype "passive"))
      (node (ref "Q56") (pin "G") (pinfunction "G_G") (pintype "passive"))
      (node (ref "Q57") (pin "G") (pinfunction "G_G") (pintype "passive"))
      (node (ref "Q58") (pin "G") (pinfunction "G_G") (pintype "passive"))
      (node (ref "RGT") (pin "6") (pinfunction "2_6") (pintype "passive"))
      (node (ref "U4") (pin "9") (pinfunction "S6_9") (pintype "passive"))
    )
    (net (code "33") (name "GT6") (class "Default")
      (node (ref "Q66") (pin "G") (pinfunction "G_G") (pintype "passive"))
      (node (ref "Q68") (pin "G") (pinfunction "G_G") (pintype "passive"))
      (node (ref "RGT") (pin "7") (pinfunction "2_7") (pintype "passive"))
      (node (ref "U4") (pin "8") (pinfunction "S7_8") (pintype "passive"))
    )
    (net (code "34") (name "Net-(DA1A-C)") (class "Default")
      (node (ref "DA1") (pin "1") (pinfunction "C_1") (pintype "passive"))
      (node (ref "DA1") (pin "2") (pinfunction "C_2") (pintype "passive"))
      (node (ref "DA1") (pin "3") (pinfunction "C_3") (pintype "passive"))
      (node (ref "R4") (pin "2") (pinfunction "2_2") (pintype "passive"))
      (node (ref "R7") (pin "1") (pinfunction "1_1") (pintype "passive"))
    )
    (net (code "35") (name "Net-(DA2A-C)") (class "Default")
      (node (ref "DA2") (pin "1") (pinfunction "C_1") (pintype "passive"))
      (node (ref "DA2") (pin "2") (pinfunction "C_2") (pintype "passive"))
      (node (ref "R5") (pin "1") (pinfunction "1_1") (pintype "passive"))
    )
    (net (code "36") (name "Net-(L1-A2)") (class "Default")
      (node (ref "L1") (pin "3") (pinfunction "A2_3") (pintype "passive"))
      (node (ref "Q1") (pin "D") (pinfunction "D_D") (pintype "passive"))
    )
    (net (code "37") (name "Net-(L1-B2)") (class "Default")
      (node (ref "DT1") (pin "A") (pinfunction "A_A") (pintype "passive"))
      (node (ref "L1") (pin "4") (pinfunction "B2_4") (pintype "passive"))
    )
    (net (code "38") (name "Net-(Q1-PadS)") (class "Default")
      (node (ref "Q1") (pin "S") (pinfunction "S_S") (pintype "passive"))
      (node (ref "R8") (pin "2") (pinfunction "2_2") (pintype "passive"))
      (node (ref "R9") (pin "2") (pinfunction "2_2") (pintype "passive"))
      (node (ref "RSSENSE") (pin "2") (pinfunction "2_2") (pintype "passive"))
    )
    (net (code "39") (name "Net-(Q3A-G)") (class "Default")
      (node (ref "Q3") (pin "2") (pinfunction "G_2") (pintype "passive"))
      (node (ref "R10") (pin "1") (pinfunction "1_1") (pintype "passive"))
      (node (ref "U3") (pin "2") (pinfunction "S1_2") (pintype "passive"))
    )
    (net (code "40") (name "Net-(Q4A-G)") (class "Default")
      (node (ref "Q4") (pin "2") (pinfunction "G_2") (pintype "passive"))
      (node (ref "R19") (pin "1") (pinfunction "1_1") (pintype "passive"))
      (node (ref "U4") (pin "3") (pinfunction "S2_3") (pintype "passive"))
    )
    (net (code "41") (name "Net-(Q21-PadS)") (class "Default")
      (node (ref "Q21") (pin "S") (pinfunction "S_S") (pintype "passive"))
      (node (ref "Q22") (pin "S") (pinfunction "S_S") (pintype "passive"))
    )
    (net (code "42") (name "Net-(Q23-PadS)") (class "Default")
      (node (ref "Q23") (pin "S") (pinfunction "S_S") (pintype "passive"))
      (node (ref "Q24") (pin "S") (pinfunction "S_S") (pintype "passive"))
    )
    (net (code "43") (name "Net-(Q25-PadS)") (class "Default")
      (node (ref "Q25") (pin "S") (pinfunction "S_S") (pintype "passive"))
      (node (ref "Q26") (pin "S") (pinfunction "S_S") (pintype "passive"))
    )
    (net (code "44") (name "Net-(Q27-PadS)") (class "Default")
      (node (ref "Q27") (pin "S") (pinfunction "S_S") (pintype "passive"))
      (node (ref "Q28") (pin "S") (pinfunction "S_S") (pintype "passive"))
    )
    (net (code "45") (name "Net-(Q31-PadS)") (class "Default")
      (node (ref "Q31") (pin "S") (pinfunction "S_S") (pintype "passive"))
      (node (ref "Q32") (pin "S") (pinfunction "S_S") (pintype "passive"))
    )
    (net (code "46") (name "Net-(Q33-PadS)") (class "Default")
      (node (ref "Q33") (pin "S") (pinfunction "S_S") (pintype "passive"))
      (node (ref "Q34") (pin "S") (pinfunction "S_S") (pintype "passive"))
    )
    (net (code "47") (name "Net-(Q35-PadS)") (class "Default")
      (node (ref "Q35") (pin "S") (pinfunction "S_S") (pintype "passive"))
      (node (ref "Q36") (pin "S") (pinfunction "S_S") (pintype "passive"))
    )
    (net (code "48") (name "Net-(Q37-PadS)") (class "Default")
      (node (ref "Q37") (pin "S") (pinfunction "S_S") (pintype "passive"))
      (node (ref "Q38") (pin "S") (pinfunction "S_S") (pintype "passive"))
    )
    (net (code "49") (name "Net-(Q41-PadS)") (class "Default")
      (node (ref "Q41") (pin "S") (pinfunction "S_S") (pintype "passive"))
      (node (ref "Q42") (pin "S") (pinfunction "S_S") (pintype "passive"))
    )
    (net (code "50") (name "Net-(Q43-PadS)") (class "Default")
      (node (ref "Q43") (pin "S") (pinfunction "S_S") (pintype "passive"))
      (node (ref "Q44") (pin "S") (pinfunction "S_S") (pintype "passive"))
    )
    (net (code "51") (name "Net-(Q45-PadS)") (class "Default")
      (node (ref "Q45") (pin "S") (pinfunction "S_S") (pintype "passive"))
      (node (ref "Q46") (pin "S") (pinfunction "S_S") (pintype "passive"))
    )
    (net (code "52") (name "Net-(Q47-PadS)") (class "Default")
      (node (ref "Q47") (pin "S") (pinfunction "S_S") (pintype "passive"))
      (node (ref "Q48") (pin "S") (pinfunction "S_S") (pintype "passive"))
    )
    (net (code "53") (name "Net-(Q51-PadS)") (class "Default")
      (node (ref "Q51") (pin "S") (pinfunction "S_S") (pintype "passive"))
      (node (ref "Q52") (pin "S") (pinfunction "S_S") (pintype "passive"))
    )
    (net (code "54") (name "Net-(Q53-PadS)") (class "Default")
      (node (ref "Q53") (pin "S") (pinfunction "S_S") (pintype "passive"))
      (node (ref "Q54") (pin "S") (pinfunction "S_S") (pintype "passive"))
    )
    (net (code "55") (name "Net-(Q55-PadS)") (class "Default")
      (node (ref "Q55") (pin "S") (pinfunction "S_S") (pintype "passive"))
      (node (ref "Q56") (pin "S") (pinfunction "S_S") (pintype "passive"))
    )
    (net (code "56") (name "Net-(Q57-PadS)") (class "Default")
      (node (ref "Q57") (pin "S") (pinfunction "S_S") (pintype "passive"))
      (node (ref "Q58") (pin "S") (pinfunction "S_S") (pintype "passive"))
    )
    (net (code "57") (name "Net-(U1-FS)") (class "Default")
      (node (ref "R6") (pin "2") (pinfunction "2_2") (pintype "passive"))
      (node (ref "U1") (pin "5") (pinfunction "FS_5") (pintype "passive"))
    )
    (net (code "58") (name "Net-(U1-GATE)") (class "Default")
      (node (ref "Q1") (pin "G") (pinfunction "G_G") (pintype "passive"))
      (node (ref "U1") (pin "6") (pinfunction "GATE_6") (pintype "passive"))
    )
    (net (code "59") (name "Net-(U1-I_SENSE)") (class "Default")
      (node (ref "R8") (pin "1") (pinfunction "1_1") (pintype "passive"))
      (node (ref "U1") (pin "9") (pinfunction "I_SENSE_9") (pintype "passive"))
    )
    (net (code "60") (name "Net-(U1-I_TH)") (class "Default")
      (node (ref "D3") (pin "A") (pinfunction "A_A") (pintype "passive"))
      (node (ref "U1") (pin "2") (pinfunction "I_TH_2") (pintype "passive"))
    )
    (net (code "61") (name "Net-(U1-OC)") (class "Default")
      (node (ref "R9") (pin "1") (pinfunction "1_1") (pintype "passive"))
      (node (ref "U1") (pin "8") (pinfunction "OC_8") (pintype "passive"))
    )
    (net (code "62") (name "S+") (class "Default")
      (node (ref "CSOURCE") (pin "2") (pinfunction "2_2") (pintype "passive"))
      (node (ref "J4") (pin "4") (pinfunction "4_4") (pintype "passive"))
      (node (ref "L1") (pin "1") (pinfunction "A1_1") (pintype "passive"))
      (node (ref "Q12") (pin "D") (pinfunction "D_D") (pintype "passive"))
      (node (ref "Q22") (pin "D") (pinfunction "D_D") (pintype "passive"))
      (node (ref "Q32") (pin "D") (pinfunction "D_D") (pintype "passive"))
      (node (ref "Q42") (pin "D") (pinfunction "D_D") (pintype "passive"))
      (node (ref "Q52") (pin "D") (pinfunction "D_D") (pintype "passive"))
      (node (ref "Q62") (pin "D") (pinfunction "D_D") (pintype "passive"))
    )
    (net (code "63") (name "S-") (class "Default")
      (node (ref "CSOURCE") (pin "1") (pinfunction "1_1") (pintype "passive"))
      (node (ref "J1") (pin "1") (pinfunction "1_1") (pintype "passive"))
      (node (ref "J4") (pin "2") (pinfunction "2_2") (pintype "passive"))
      (node (ref "Q14") (pin "D") (pinfunction "D_D") (pintype "passive"))
      (node (ref "Q24") (pin "D") (pinfunction "D_D") (pintype "passive"))
      (node (ref "Q34") (pin "D") (pinfunction "D_D") (pintype "passive"))
      (node (ref "Q44") (pin "D") (pinfunction "D_D") (pintype "passive"))
      (node (ref "Q54") (pin "D") (pinfunction "D_D") (pintype "passive"))
      (node (ref "Q64") (pin "D") (pinfunction "D_D") (pintype "passive"))
      (node (ref "RSSENSE") (pin "1") (pinfunction "1_1") (pintype "passive"))
    )
    (net (code "64") (name "S-F") (class "Default")
      (node (ref "C2") (pin "1") (pinfunction "1_1") (pintype "passive"))
      (node (ref "C8") (pin "1") (pinfunction "1_1") (pintype "passive"))
      (node (ref "J2") (pin "3") (pinfunction "3_3") (pintype "passive"))
      (node (ref "J3") (pin "2") (pinfunction "2_2") (pintype "passive"))
      (node (ref "R16") (pin "1") (pinfunction "1_1") (pintype "passive"))
      (node (ref "R6") (pin "1") (pinfunction "1_1") (pintype "passive"))
      (node (ref "RA") (pin "4") (pinfunction "1_4") (pintype "passive"))
      (node (ref "RA") (pin "5") (pinfunction "2_5") (pintype "passive"))
      (node (ref "RA") (pin "6") (pinfunction "2_6") (pintype "passive"))
      (node (ref "RA") (pin "7") (pinfunction "2_7") (pintype "passive"))
      (node (ref "RA") (pin "8") (pinfunction "2_8") (pintype "passive"))
      (node (ref "U1") (pin "10") (pinfunction "SYNC_10") (pintype "passive"))
      (node (ref "U1") (pin "3") (pinfunction "FB_3") (pintype "passive"))
      (node (ref "U1") (pin "PAD") (pinfunction "GND_PAD") (pintype "power_in"))
      (node (ref "U2") (pin "3") (pinfunction "GND_3") (pintype "passive"))
      (node (ref "U2") (pin "PAD") (pinfunction "GND_PAD") (pintype "passive"))
      (node (ref "U3") (pin "12") (pinfunction "GND_12") (pintype "passive"))
      (node (ref "U4") (pin "12") (pinfunction "GND_12") (pintype "passive"))
    )
    (net (code "65") (name "SCL") (class "Default")
      (node (ref "J3") (pin "4") (pinfunction "4_4") (pintype "passive"))
      (node (ref "U2") (pin "1") (pinfunction "PA2_1") (pintype "passive"))
    )
    (net (code "66") (name "SDA") (class "Default")
      (node (ref "J3") (pin "3") (pinfunction "3_3") (pintype "passive"))
      (node (ref "U2") (pin "20") (pinfunction "PA1_20") (pintype "passive"))
    )
    (net (code "67") (name "T+") (class "Default")
      (node (ref "CTARGET") (pin "2") (pinfunction "2_2") (pintype "passive"))
      (node (ref "DT1") (pin "C") (pinfunction "C_C") (pintype "passive"))
      (node (ref "J1") (pin "4") (pinfunction "4_4") (pintype "passive"))
      (node (ref "J2") (pin "1") (pinfunction "1_1") (pintype "passive"))
      (node (ref "Q16") (pin "D") (pinfunction "D_D") (pintype "passive"))
      (node (ref "Q26") (pin "D") (pinfunction "D_D") (pintype "passive"))
      (node (ref "Q36") (pin "D") (pinfunction "D_D") (pintype "passive"))
      (node (ref "Q46") (pin "D") (pinfunction "D_D") (pintype "passive"))
      (node (ref "Q56") (pin "D") (pinfunction "D_D") (pintype "passive"))
      (node (ref "Q66") (pin "D") (pinfunction "D_D") (pintype "passive"))
      (node (ref "R2") (pin "2") (pinfunction "2_2") (pintype "passive"))
    )
    (net (code "68") (name "T-") (class "Default")
      (node (ref "CTARGET") (pin "1") (pinfunction "1_1") (pintype "passive"))
      (node (ref "J1") (pin "3") (pinfunction "3_3") (pintype "passive"))
      (node (ref "J2") (pin "2") (pinfunction "2_2") (pintype "passive"))
      (node (ref "L1") (pin "2") (pinfunction "B1_2") (pintype "passive"))
      (node (ref "Q18") (pin "D") (pinfunction "D_D") (pintype "passive"))
      (node (ref "Q28") (pin "D") (pinfunction "D_D") (pintype "passive"))
      (node (ref "Q38") (pin "D") (pinfunction "D_D") (pintype "passive"))
      (node (ref "Q48") (pin "D") (pinfunction "D_D") (pintype "passive"))
      (node (ref "Q58") (pin "D") (pinfunction "D_D") (pintype "passive"))
      (node (ref "Q68") (pin "D") (pinfunction "D_D") (pintype "passive"))
      (node (ref "R2") (pin "1") (pinfunction "1_1") (pintype "passive"))
    )
    (net (code "69") (name "TH") (class "Default")
      (node (ref "D3") (pin "C") (pinfunction "C_C") (pintype "passive"))
      (node (ref "J2") (pin "4") (pinfunction "4_4") (pintype "passive"))
      (node (ref "U2") (pin "10") (pinfunction "PB4_10") (pintype "passive"))
    )
    (net (code "70") (name "unconnected-(U1-SSFLT-Pad1)") (class "Default")
      (node (ref "U1") (pin "1") (pinfunction "SSFLT_1") (pintype "passive"))
    )
    (net (code "71") (name "unconnected-(U2-PA7-Pad8)") (class "Default")
      (node (ref "U2") (pin "8") (pinfunction "PA7_8") (pintype "passive"))
    )
    (net (code "72") (name "unconnected-(U2-PB3-Pad11)") (class "Default")
      (node (ref "U2") (pin "11") (pinfunction "PB3_11") (pintype "passive"))
    )
    (net (code "73") (name "unconnected-(U2-PB5-Pad9)") (class "Default")
      (node (ref "U2") (pin "9") (pinfunction "PB5_9") (pintype "passive"))
    )
    (net (code "74") (name "unconnected-(U2-PC0-Pad15)") (class "Default")
      (node (ref "U2") (pin "15") (pinfunction "PC0_15") (pintype "passive"))
    )
    (net (code "75") (name "unconnected-(U2-PC1-Pad16)") (class "Default")
      (node (ref "U2") (pin "16") (pinfunction "PC1_16") (pintype "passive"))
    )
    (net (code "76") (name "unconnected-(U2-PC2-Pad17)") (class "Default")
      (node (ref "U2") (pin "17") (pinfunction "PC2_17") (pintype "passive"))
    )
    (net (code "77") (name "unconnected-(U2-PC3-Pad18)") (class "Default")
      (node (ref "U2") (pin "18") (pinfunction "PC3_18") (pintype "passive"))
    )
  )
)
